# HIVE_SIGHT_MISC.net
KiCad netlist of a schematic drawn in Altium Designer
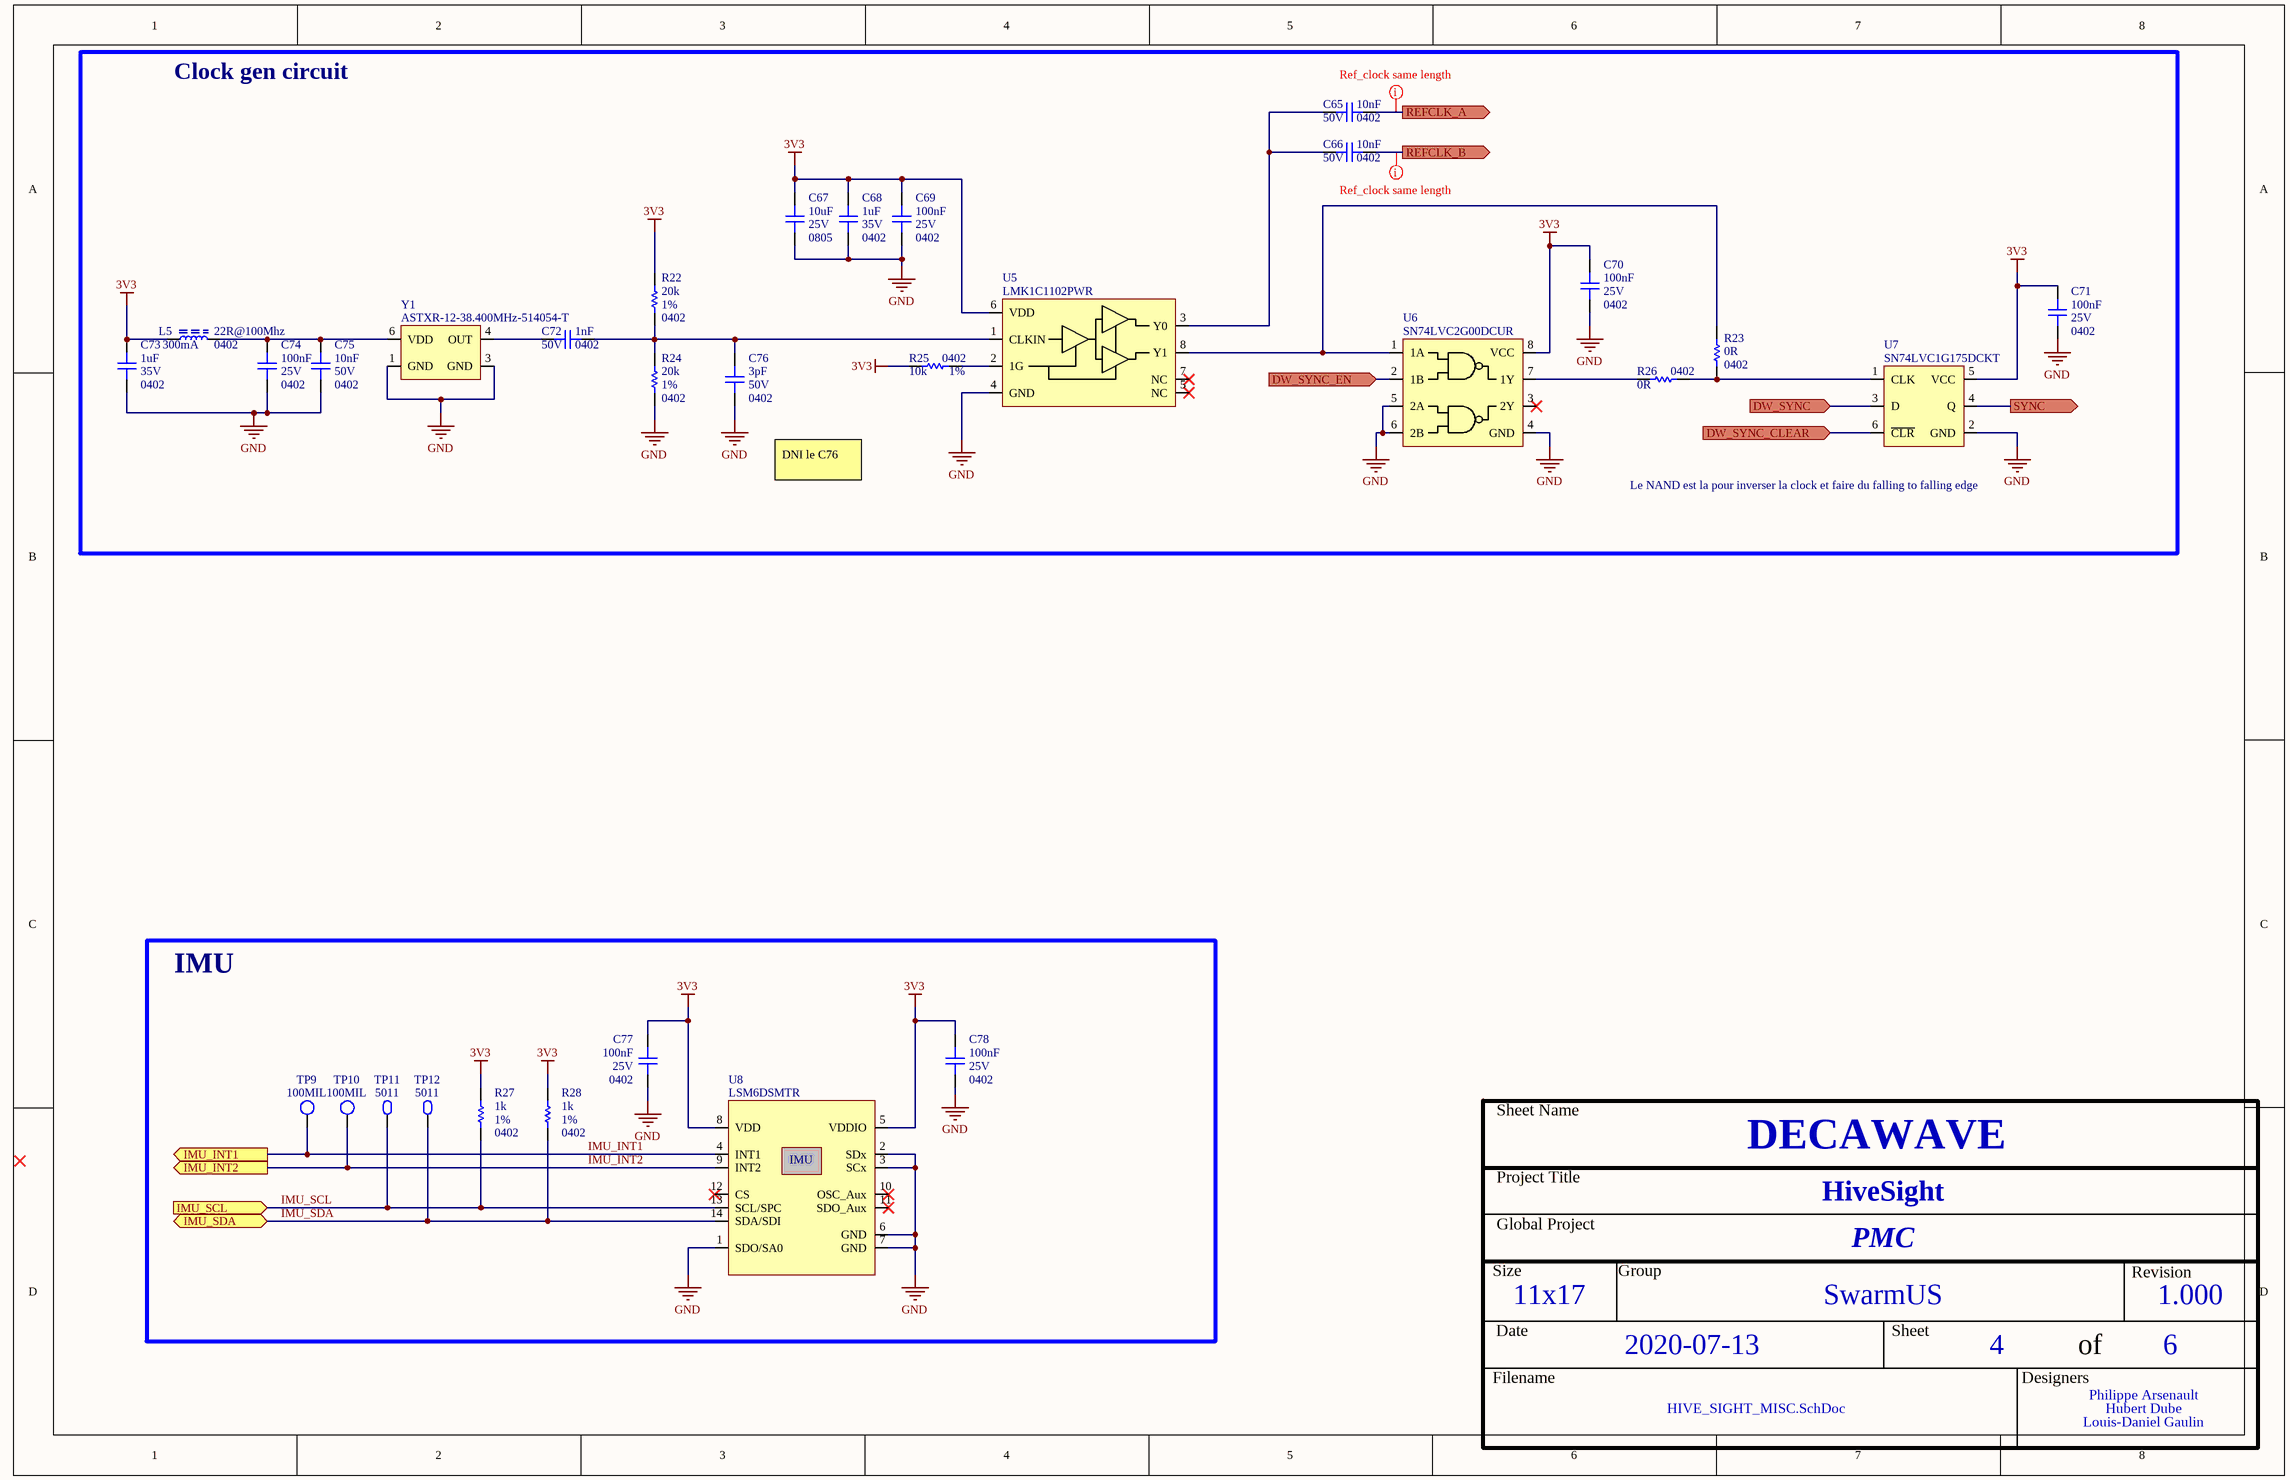
[diagram p0: HIVE_SIGHT_MISC.SchDoc]

(export (version "E")
  (design (tool "Eeschema 10.0.6"))
  (components
    (comp (ref "C65")
      (value "10nF")
      (footprint "GRAMS_MASTER_LIB_PCB:CAP_CER_0402")
      (description "CAP - CER 10nF 50V X7R 20% - 0402")
      (fields
        (field (name "TOLERANCE") "20%")
        (field (name "PACKAGE") "0402")
        (field (name "VOLTAGE RATING") "50V")
        (field (name "Comment") "C0402C103M5RACTU")
        (field (name "CREATEDBY/DATE") "Keven Deslandes - 2018/11/09")
        (field (name "VERIFIEDBY") "Nicolas Roy - 2018/12/11")
      )
      (libsource (lib "GRAMS_MASTER_LIB_SCH") (part "CAP_CER_C0402C103M5RACTU"))
    )
    (comp (ref "C66")
      (value "10nF")
      (footprint "GRAMS_MASTER_LIB_PCB:CAP_CER_0402")
      (description "CAP - CER 10nF 50V X7R 20% - 0402")
      (fields
        (field (name "TOLERANCE") "20%")
        (field (name "PACKAGE") "0402")
        (field (name "VOLTAGE RATING") "50V")
        (field (name "Comment") "C0402C103M5RACTU")
        (field (name "CREATEDBY/DATE") "Keven Deslandes - 2018/11/09")
        (field (name "VERIFIEDBY") "Nicolas Roy - 2018/12/11")
      )
      (libsource (lib "GRAMS_MASTER_LIB_SCH") (part "CAP_CER_C0402C103M5RACTU"))
    )
    (comp (ref "C67")
      (value "10uF")
      (footprint "GRAMS_MASTER_LIB_PCB:CAP_CER_0805")
      (description "CAP - CER 10UF 10% 25V X7S - 0805")
      (fields
        (field (name "TOLERANCE") "10%")
        (field (name "PACKAGE") "0805")
        (field (name "VOLTAGE RATING") "25V")
        (field (name "Comment") "GRM21BC71E106KE11L")
        (field (name "CREATEDBY/DATE") "Caroline Paulin / 8 août 2018")
        (field (name "VERIFIEDBY") "Nicolas V. (2019-01-22)")
      )
      (libsource (lib "GRAMS_MASTER_LIB_SCH") (part "CAP_CER_GRM21BC71E106KE11L"))
    )
    (comp (ref "C68")
      (value "1uF")
      (footprint "GRAMS_MASTER_LIB_PCB:CAP_CER_0402")
      (description "CAP - CER 1uF 10% 35V X5R - 0402")
      (fields
        (field (name "TOLERANCE") "10%")
        (field (name "PACKAGE") "0402")
        (field (name "VOLTAGE RATING") "35V")
        (field (name "Comment") "CL05A105KL5NRNC")
        (field (name "CREATEDBY/DATE") "Nicolas Roy 2018-10-03")
        (field (name "VERIFIEDBY") "Caroline Paulin - 18 janv 2019")
      )
      (libsource (lib "GRAMS_MASTER_LIB_SCH") (part "CAP_CER_CL05A105KL5NRNC"))
    )
    (comp (ref "C69")
      (value "100nF")
      (footprint "GRAMS_MASTER_LIB_PCB:CAP_CER_0402")
      (description "CAP - CER 0.1uF 10% 25V X5R - 0402")
      (fields
        (field (name "TOLERANCE") "10%")
        (field (name "PACKAGE") "0402")
        (field (name "VOLTAGE RATING") "25V")
        (field (name "Comment") "CL05A104KA5NNNC")
        (field (name "CREATEDBY/DATE") "Keven Deslandes - 2018/09/26")
        (field (name "VERIFIEDBY") "Nicolas Roy - 2018/12/11")
      )
      (libsource (lib "GRAMS_MASTER_LIB_SCH") (part "CAP_CER_CL05A104KA5NNNC"))
    )
    (comp (ref "C70")
      (value "100nF")
      (footprint "GRAMS_MASTER_LIB_PCB:CAP_CER_0402")
      (description "CAP - CER 0.1uF 10% 25V X5R - 0402")
      (fields
        (field (name "TOLERANCE") "10%")
        (field (name "PACKAGE") "0402")
        (field (name "VOLTAGE RATING") "25V")
        (field (name "Comment") "CL05A104KA5NNNC")
        (field (name "CREATEDBY/DATE") "Keven Deslandes - 2018/09/26")
        (field (name "VERIFIEDBY") "Nicolas Roy - 2018/12/11")
      )
      (libsource (lib "GRAMS_MASTER_LIB_SCH") (part "CAP_CER_CL05A104KA5NNNC"))
    )
    (comp (ref "C71")
      (value "100nF")
      (footprint "GRAMS_MASTER_LIB_PCB:CAP_CER_0402")
      (description "CAP - CER 0.1uF 10% 25V X5R - 0402")
      (fields
        (field (name "TOLERANCE") "10%")
        (field (name "PACKAGE") "0402")
        (field (name "VOLTAGE RATING") "25V")
        (field (name "Comment") "CL05A104KA5NNNC")
        (field (name "CREATEDBY/DATE") "Keven Deslandes - 2018/09/26")
        (field (name "VERIFIEDBY") "Nicolas Roy - 2018/12/11")
      )
      (libsource (lib "GRAMS_MASTER_LIB_SCH") (part "CAP_CER_CL05A104KA5NNNC"))
    )
    (comp (ref "C72")
      (value "1nF")
      (footprint "CAP_CER_0402")
      (description "CAP - CER 1nF 10% 50V X7R - 0402")
      (fields
        (field (name "TOLERANCE") "10%")
        (field (name "PACKAGE") "0402")
        (field (name "VOLTAGE RATING") "50V")
        (field (name "Comment") "CC0402KRX7R9BB102")
        (field (name "CREATEDBY/DATE") "Jonathan Bouchard 2019-04-06")
        (field (name "VERIFIEDBY") "Nicolas V. (2019-04-30)")
      )
      (libsource (lib "GRAMS_MASTER_LIB_SCH") (part "CAP_CER_CC0402KRX7R9BB102"))
    )
    (comp (ref "C73")
      (value "1uF")
      (footprint "GRAMS_MASTER_LIB_PCB:CAP_CER_0402")
      (description "CAP - CER 1uF 10% 35V X5R - 0402")
      (fields
        (field (name "TOLERANCE") "10%")
        (field (name "PACKAGE") "0402")
        (field (name "VOLTAGE RATING") "35V")
        (field (name "Comment") "CL05A105KL5NRNC")
        (field (name "CREATEDBY/DATE") "Nicolas Roy 2018-10-03")
        (field (name "VERIFIEDBY") "Caroline Paulin - 18 janv 2019")
      )
      (libsource (lib "GRAMS_MASTER_LIB_SCH") (part "CAP_CER_CL05A105KL5NRNC"))
    )
    (comp (ref "C74")
      (value "100nF")
      (footprint "GRAMS_MASTER_LIB_PCB:CAP_CER_0402")
      (description "CAP - CER 0.1uF 10% 25V X5R - 0402")
      (fields
        (field (name "TOLERANCE") "10%")
        (field (name "PACKAGE") "0402")
        (field (name "VOLTAGE RATING") "25V")
        (field (name "Comment") "CL05A104KA5NNNC")
        (field (name "CREATEDBY/DATE") "Keven Deslandes - 2018/09/26")
        (field (name "VERIFIEDBY") "Nicolas Roy - 2018/12/11")
      )
      (libsource (lib "GRAMS_MASTER_LIB_SCH") (part "CAP_CER_CL05A104KA5NNNC"))
    )
    (comp (ref "C75")
      (value "10nF")
      (footprint "GRAMS_MASTER_LIB_PCB:CAP_CER_0402")
      (description "CAP - CER 10nF 50V X7R 20% - 0402")
      (fields
        (field (name "TOLERANCE") "20%")
        (field (name "PACKAGE") "0402")
        (field (name "VOLTAGE RATING") "50V")
        (field (name "Comment") "C0402C103M5RACTU")
        (field (name "CREATEDBY/DATE") "Keven Deslandes - 2018/11/09")
        (field (name "VERIFIEDBY") "Nicolas Roy - 2018/12/11")
      )
      (libsource (lib "GRAMS_MASTER_LIB_SCH") (part "CAP_CER_C0402C103M5RACTU"))
    )
    (comp (ref "C76")
      (value "3pF")
      (footprint "CAP_CER_0402")
      (description "CAP - CER 3pF 50V ±0.25pF C0G, NP0 - 0402")
      (fields
        (field (name "TOLERANCE") "±0.25pF")
        (field (name "PACKAGE") "0402")
        (field (name "VOLTAGE RATING") "50V")
        (field (name "Comment") "CC0402CRNPO9BN3R0")
        (field (name "CREATEDBY/DATE") "Philippe Arsenault/ 2020-07-24")
        (field (name "VERIFIEDBY") "Louis-Daniel Gaulin / 2020-07-29")
      )
      (libsource (lib "SWARMUS_LIB") (part "CAP_CER_CC0402CRNPO9BN3R0"))
    )
    (comp (ref "C77")
      (value "100nF")
      (footprint "GRAMS_MASTER_LIB_PCB:CAP_CER_0402")
      (description "CAP - CER 0.1µF 10% 25V X7R - 0402")
      (fields
        (field (name "TOLERANCE") "10%")
        (field (name "PACKAGE") "0402")
        (field (name "VOLTAGE RATING") "25V")
        (field (name "Comment") "CGA2B3X7R1E104K050BB")
        (field (name "CREATEDBY/DATE") "Nicolas Roy 2018-11-07")
        (field (name "VERIFIEDBY") "Nicolas V. (2019-01-22)")
      )
      (libsource (lib "GRAMS_MASTER_LIB_SCH") (part "CAP_CER_CGA2B3X7R1E104K050BB"))
    )
    (comp (ref "C78")
      (value "100nF")
      (footprint "GRAMS_MASTER_LIB_PCB:CAP_CER_0402")
      (description "CAP - CER 0.1µF 10% 25V X7R - 0402")
      (fields
        (field (name "TOLERANCE") "10%")
        (field (name "PACKAGE") "0402")
        (field (name "VOLTAGE RATING") "25V")
        (field (name "Comment") "CGA2B3X7R1E104K050BB")
        (field (name "CREATEDBY/DATE") "Nicolas Roy 2018-11-07")
        (field (name "VERIFIEDBY") "Nicolas V. (2019-01-22)")
      )
      (libsource (lib "GRAMS_MASTER_LIB_SCH") (part "CAP_CER_CGA2B3X7R1E104K050BB"))
    )
    (comp (ref "L5")
      (value "22R@100Mhz")
      (footprint "FER_0402")
      (description "FER - FERRITE BEAD 22 OHM - 0402")
      (fields
        (field (name "CURRENT RATING") "300mA")
        (field (name "PACKAGE") "0402")
        (field (name "Comment") "BLM15BB220SN1D")
        (field (name "CREATEDBY/DATE") "Philippe Arsenault/2020-11-03")
      )
      (libsource (lib "a_Valider_PA") (part "FER_BLM15BB220SN1D"))
    )
    (comp (ref "R22")
      (value "20k")
      (footprint "GRAMS_MASTER_LIB_PCB:RES_0402")
      (description "RES - 20K 1% 1/16W  - 0402")
      (fields
        (field (name "TOLERANCE") "1%")
        (field (name "PACKAGE") "0402")
        (field (name "Comment") "RC0402FR-0720KL")
        (field (name "CREATEDBY/DATE") "Keven Deslandes 2018-10-18")
        (field (name "VERIFIEDBY") "Caroline Paulin - 7 janv 2019")
      )
      (libsource (lib "GRAMS_MASTER_LIB_SCH") (part "RES_RC0402FR-0720KL"))
    )
    (comp (ref "R23")
      (value "0R")
      (footprint "GRAMS_MASTER_LIB_PCB:RES_0402")
      (description "RES - 0R 1/16W 1A  - 0402")
      (fields
        (field (name "PACKAGE") "0402")
        (field (name "Comment") "RC0402FR-070RL")
        (field (name "CREATEDBY/DATE") "Keven Deslandes 2018-09-12")
        (field (name "VERIFIEDBY") "Caroline Paulin - 27 fév 2019")
      )
      (libsource (lib "GRAMS_MASTER_LIB_SCH") (part "RES_RC0402FR-070RL"))
    )
    (comp (ref "R24")
      (value "20k")
      (footprint "GRAMS_MASTER_LIB_PCB:RES_0402")
      (description "RES - 20K 1% 1/16W  - 0402")
      (fields
        (field (name "TOLERANCE") "1%")
        (field (name "PACKAGE") "0402")
        (field (name "Comment") "RC0402FR-0720KL")
        (field (name "CREATEDBY/DATE") "Keven Deslandes 2018-10-18")
        (field (name "VERIFIEDBY") "Caroline Paulin - 7 janv 2019")
      )
      (libsource (lib "GRAMS_MASTER_LIB_SCH") (part "RES_RC0402FR-0720KL"))
    )
    (comp (ref "R25")
      (value "10k")
      (footprint "GRAMS_MASTER_LIB_PCB:RES_0402")
      (description "RES - 10K OHMS 1% 1/16W - 0402")
      (fields
        (field (name "TOLERANCE") "1%")
        (field (name "PACKAGE") "0402")
        (field (name "Comment") "RC0402FR-0710KL")
        (field (name "CREATEDBY/DATE") "Nicolas V. (2018-11-20)")
        (field (name "VERIFIEDBY") "Nicolas V. (2018-11-20)")
      )
      (libsource (lib "GRAMS_MASTER_LIB_SCH") (part "RES_RC0402FR-0710KL"))
    )
    (comp (ref "R26")
      (value "0R")
      (footprint "GRAMS_MASTER_LIB_PCB:RES_0402")
      (description "RES - 0R 1/16W 1A  - 0402")
      (fields
        (field (name "PACKAGE") "0402")
        (field (name "Comment") "RC0402FR-070RL")
        (field (name "CREATEDBY/DATE") "Keven Deslandes 2018-09-12")
        (field (name "VERIFIEDBY") "Caroline Paulin - 27 fév 2019")
      )
      (libsource (lib "GRAMS_MASTER_LIB_SCH") (part "RES_RC0402FR-070RL"))
    )
    (comp (ref "R27")
      (value "1k")
      (footprint "GRAMS_MASTER_LIB_PCB:RES_0402")
      (description "RES - 1K OHM 1% 1/16W - 0402")
      (fields
        (field (name "TOLERANCE") "1%")
        (field (name "PACKAGE") "0402")
        (field (name "Comment") "RC0402FR-071KL")
        (field (name "CREATEDBY/DATE") "Jonathan Bouchard 2018-07-05")
        (field (name "VERIFIEDBY") "Arnaud Samson 16-07-18")
      )
      (libsource (lib "GRAMS_MASTER_LIB_SCH") (part "RES_RC0402FR-071KL"))
    )
    (comp (ref "R28")
      (value "1k")
      (footprint "GRAMS_MASTER_LIB_PCB:RES_0402")
      (description "RES - 1K OHM 1% 1/16W - 0402")
      (fields
        (field (name "TOLERANCE") "1%")
        (field (name "PACKAGE") "0402")
        (field (name "Comment") "RC0402FR-071KL")
        (field (name "CREATEDBY/DATE") "Jonathan Bouchard 2018-07-05")
        (field (name "VERIFIEDBY") "Arnaud Samson 16-07-18")
      )
      (libsource (lib "GRAMS_MASTER_LIB_SCH") (part "RES_RC0402FR-071KL"))
    )
    (comp (ref "TP9")
      (value "100MIL")
      (footprint "grams_master_lib_pcb:TPO_TH_ROUND_100MIL")
      (description "TPO - TEST POINT ROUND TH  - 100MIL")
      (fields
        (field (name "CREATEDBY/DATE") "Louis-Daniel Gaulin/ 14/01/2020")
        (field (name "VERIFIEDBY") "C.Paulin - 21/01/2020")
      )
      (libsource (lib "GRAMS_MASTER_LIB_SCH") (part "TPO_TH_ROUND_100MIL"))
    )
    (comp (ref "TP10")
      (value "100MIL")
      (footprint "grams_master_lib_pcb:TPO_TH_ROUND_100MIL")
      (description "TPO - TEST POINT ROUND TH  - 100MIL")
      (fields
        (field (name "CREATEDBY/DATE") "Louis-Daniel Gaulin/ 14/01/2020")
        (field (name "VERIFIEDBY") "C.Paulin - 21/01/2020")
      )
      (libsource (lib "GRAMS_MASTER_LIB_SCH") (part "TPO_TH_ROUND_100MIL"))
    )
    (comp (ref "TP11")
      (value "5011")
      (footprint "TPO_5011")
      (description "TPO - TEST POINT - TH")
      (fields
        (field (name "CREATEDBY/DATE") "Louis-Daniel Gauli / 02-11-2020")
        (field (name "VERIFIEDBY") "Philippe Arsenault/2020-11-06")
      )
      (libsource (lib "SWARMUS_LIB") (part "TPO_5011"))
    )
    (comp (ref "TP12")
      (value "5011")
      (footprint "TPO_5011")
      (description "TPO - TEST POINT - TH")
      (fields
        (field (name "CREATEDBY/DATE") "Louis-Daniel Gauli / 02-11-2020")
        (field (name "VERIFIEDBY") "Philippe Arsenault/2020-11-06")
      )
      (libsource (lib "SWARMUS_LIB") (part "TPO_5011"))
    )
    (comp (ref "U5")
      (value "LMK1C1102PWR")
      (footprint "COM_BUF_LMK1C1102PWR")
      (description "COM - BUF - Clock buffer 3V3, 2V5, 1V8 2 Channel - TSSOP 8")
      (fields
        (field (name "CREATEDBY/DATE") "Philippe Arsenault/20-07-2020")
        (field (name "VERIFIEDBY") "Louis-Daniel Gaulin / 23-07-2020")
      )
      (libsource (lib "SWARMUS_LIB") (part "COM_BUF_LMK1C1102PWR"))
    )
    (comp (ref "U6")
      (value "SN74LVC2G00DCUR")
      (footprint "LOG_NAND_SN74LVC2G00DCUR")
      (description "LOG_NAND - GATE NAND 2CH 2-INP - 8-VSSOP")
      (fields
        (field (name "CREATEDBY/DATE") "Philippe Arsenault/21-07-2020")
        (field (name "VERIFIEDBY") "Louis-Daniel Gaulin / 23-07-2020")
      )
      (libsource (lib "SWARMUS_LIB") (part "LOG_NAND_SN74LVC2G00DCUR"))
    )
    (comp (ref "U7")
      (value "SN74LVC1G175DCKT")
      (footprint "LOG_FLIPFLOP_SN74LVC1G175DCKT")
      (description "LOG_FLIPFLOP - Single D flip-flop with Asynchronous clear - SOT-363")
      (fields
        (field (name "CREATEDBY/DATE") "Philippe Arsenault/21-07-2020")
        (field (name "VERIFIEDBY") "Louis-Daniel Gaulin / 03-10-2020")
      )
      (libsource (lib "SWARMUS_LIB") (part "LOG_FLIPFLOP_SN74LVC1G175DCKT"))
    )
    (comp (ref "U8")
      (value "LSM6DSMTR")
      (footprint "SEN_IMU_LSM6DSMTR")
      (description "SEN_IMU -  ACCEL/GYRO 6 Axis I2C/SPI - 14-VFLGA")
      (fields
        (field (name "CREATEDBY/DATE") "Louis-Daniel Gaulin / 06-10-2020")
        (field (name "VERIFIEDBY") "Philippe Arsenault/2020-11-06")
      )
      (libsource (lib "SWARMUS_LIB") (part "SEN_IMU_LSM6DSMTR"))
    )
    (comp (ref "Y1")
      (value "ASTXR-12-38.400MHz-514054-T")
      (footprint "OSC_ASTXR-12-38.400MHZ-514054-T")
      (fields
        (field (name "CREATEDBY/DATE") "Philippe Arsenault/18-07-2020")
        (field (name "VERIFIEDBY") "Louis-Daniel Gaulin / 03-10-2020")
      )
      (libsource (lib "SWARMUS_LIB") (part "OSC_ASTXR-12-38.400MHz-514054-T"))
    )
  )
  (nets
    (net (code "1") (name "/DW_SYNC") (class "Default")
      (node (ref "U7") (pin "3") (pinfunction "D_3") (pintype "passive"))
    )
    (net (code "2") (name "/DW_SYNC_CLEAR") (class "Default")
      (node (ref "U7") (pin "6") (pinfunction "CLR_6") (pintype "passive"))
    )
    (net (code "3") (name "/DW_SYNC_EN") (class "Default")
      (node (ref "U6") (pin "2") (pinfunction "1B_2") (pintype "passive"))
    )
    (net (code "4") (name "/IMU_INT1") (class "Default")
      (node (ref "TP9") (pin "1") (pinfunction "1_1") (pintype "passive"))
      (node (ref "U8") (pin "4") (pinfunction "INT1_4") (pintype "passive"))
    )
    (net (code "5") (name "/IMU_INT2") (class "Default")
      (node (ref "TP10") (pin "1") (pinfunction "1_1") (pintype "passive"))
      (node (ref "U8") (pin "9") (pinfunction "INT2_9") (pintype "passive"))
    )
    (net (code "6") (name "/IMU_SCL") (class "Default")
      (node (ref "R27") (pin "2") (pinfunction "2_2") (pintype "passive"))
      (node (ref "TP11") (pin "1") (pinfunction "1_1") (pintype "passive"))
      (node (ref "U8") (pin "13") (pinfunction "SCL/SPC_13") (pintype "passive"))
    )
    (net (code "7") (name "/IMU_SDA") (class "Default")
      (node (ref "R28") (pin "2") (pinfunction "2_2") (pintype "passive"))
      (node (ref "TP12") (pin "1") (pinfunction "1_1") (pintype "passive"))
      (node (ref "U8") (pin "14") (pinfunction "SDA/SDI_14") (pintype "passive"))
    )
    (net (code "8") (name "/REFCLK_A") (class "Default")
      (node (ref "C65") (pin "1") (pinfunction "1_1") (pintype "passive"))
    )
    (net (code "9") (name "/REFCLK_B") (class "Default")
      (node (ref "C66") (pin "1") (pinfunction "1_1") (pintype "passive"))
    )
    (net (code "10") (name "/SYNC") (class "Default")
      (node (ref "U7") (pin "4") (pinfunction "Q_4") (pintype "passive"))
    )
    (net (code "11") (name "3V3") (class "Default")
      (node (ref "C67") (pin "2") (pinfunction "2_2") (pintype "passive"))
      (node (ref "C68") (pin "2") (pinfunction "2_2") (pintype "passive"))
      (node (ref "C69") (pin "2") (pinfunction "2_2") (pintype "passive"))
      (node (ref "C70") (pin "2") (pinfunction "2_2") (pintype "passive"))
      (node (ref "C71") (pin "1") (pinfunction "1_1") (pintype "passive"))
      (node (ref "C73") (pin "2") (pinfunction "2_2") (pintype "passive"))
      (node (ref "C77") (pin "1") (pinfunction "1_1") (pintype "passive"))
      (node (ref "C78") (pin "1") (pinfunction "1_1") (pintype "passive"))
      (node (ref "L5") (pin "1") (pinfunction "1_1") (pintype "passive"))
      (node (ref "R22") (pin "2") (pinfunction "2_2") (pintype "passive"))
      (node (ref "R25") (pin "2") (pinfunction "2_2") (pintype "passive"))
      (node (ref "R27") (pin "1") (pinfunction "1_1") (pintype "passive"))
      (node (ref "R28") (pin "1") (pinfunction "1_1") (pintype "passive"))
      (node (ref "U5") (pin "6") (pinfunction "VDD_6") (pintype "passive"))
      (node (ref "U6") (pin "8") (pinfunction "VCC_8") (pintype "passive"))
      (node (ref "U7") (pin "5") (pinfunction "VCC_5") (pintype "passive"))
      (node (ref "U8") (pin "5") (pinfunction "VDDIO_5") (pintype "passive"))
      (node (ref "U8") (pin "8") (pinfunction "VDD_8") (pintype "passive"))
    )
    (net (code "12") (name "GND") (class "Default")
      (node (ref "C67") (pin "1") (pinfunction "1_1") (pintype "passive"))
      (node (ref "C68") (pin "1") (pinfunction "1_1") (pintype "passive"))
      (node (ref "C69") (pin "1") (pinfunction "1_1") (pintype "passive"))
      (node (ref "C70") (pin "1") (pinfunction "1_1") (pintype "passive"))
      (node (ref "C71") (pin "2") (pinfunction "2_2") (pintype "passive"))
      (node (ref "C73") (pin "1") (pinfunction "1_1") (pintype "passive"))
      (node (ref "C74") (pin "1") (pinfunction "1_1") (pintype "passive"))
      (node (ref "C75") (pin "1") (pinfunction "1_1") (pintype "passive"))
      (node (ref "C76") (pin "1") (pinfunction "1_1") (pintype "passive"))
      (node (ref "C77") (pin "2") (pinfunction "2_2") (pintype "passive"))
      (node (ref "C78") (pin "2") (pinfunction "2_2") (pintype "passive"))
      (node (ref "R24") (pin "1") (pinfunction "1_1") (pintype "passive"))
      (node (ref "U5") (pin "4") (pinfunction "GND_4") (pintype "passive"))
      (node (ref "U6") (pin "4") (pinfunction "GND_4") (pintype "passive"))
      (node (ref "U6") (pin "5") (pinfunction "2A_5") (pintype "passive"))
      (node (ref "U6") (pin "6") (pinfunction "2B_6") (pintype "passive"))
      (node (ref "U7") (pin "2") (pinfunction "GND_2") (pintype "passive"))
      (node (ref "U8") (pin "1") (pinfunction "SDO/SA0_1") (pintype "passive"))
      (node (ref "U8") (pin "2") (pinfunction "SDx_2") (pintype "passive"))
      (node (ref "U8") (pin "3") (pinfunction "SCx_3") (pintype "passive"))
      (node (ref "U8") (pin "6") (pinfunction "GND_6") (pintype "passive"))
      (node (ref "U8") (pin "7") (pinfunction "GND_7") (pintype "passive"))
      (node (ref "Y1") (pin "1") (pinfunction "GND_1") (pintype "passive"))
      (node (ref "Y1") (pin "3") (pinfunction "GND_3") (pintype "passive"))
    )
    (net (code "13") (name "Net-(U5-1G)") (class "Default")
      (node (ref "R25") (pin "1") (pinfunction "1_1") (pintype "passive"))
      (node (ref "U5") (pin "2") (pinfunction "1G_2") (pintype "passive"))
    )
    (net (code "14") (name "Net-(U5-CLKIN)") (class "Default")
      (node (ref "C72") (pin "1") (pinfunction "1_1") (pintype "passive"))
      (node (ref "C76") (pin "2") (pinfunction "2_2") (pintype "passive"))
      (node (ref "R22") (pin "1") (pinfunction "1_1") (pintype "passive"))
      (node (ref "R24") (pin "2") (pinfunction "2_2") (pintype "passive"))
      (node (ref "U5") (pin "1") (pinfunction "CLKIN_1") (pintype "passive"))
    )
    (net (code "15") (name "Net-(U5-Y0)") (class "Default")
      (node (ref "C65") (pin "2") (pinfunction "2_2") (pintype "passive"))
      (node (ref "C66") (pin "2") (pinfunction "2_2") (pintype "passive"))
      (node (ref "U5") (pin "3") (pinfunction "Y0_3") (pintype "passive"))
    )
    (net (code "16") (name "Net-(U5-Y1)") (class "Default")
      (node (ref "R23") (pin "2") (pinfunction "2_2") (pintype "passive"))
      (node (ref "U5") (pin "8") (pinfunction "Y1_8") (pintype "passive"))
      (node (ref "U6") (pin "1") (pinfunction "1A_1") (pintype "passive"))
    )
    (net (code "17") (name "Net-(U6-1Y)") (class "Default")
      (node (ref "R26") (pin "2") (pinfunction "2_2") (pintype "passive"))
      (node (ref "U6") (pin "7") (pinfunction "1Y_7") (pintype "passive"))
    )
    (net (code "18") (name "Net-(U7-CLK)") (class "Default")
      (node (ref "R23") (pin "1") (pinfunction "1_1") (pintype "passive"))
      (node (ref "R26") (pin "1") (pinfunction "1_1") (pintype "passive"))
      (node (ref "U7") (pin "1") (pinfunction "CLK_1") (pintype "passive"))
    )
    (net (code "19") (name "Net-(Y1-OUT)") (class "Default")
      (node (ref "C72") (pin "2") (pinfunction "2_2") (pintype "passive"))
      (node (ref "Y1") (pin "4") (pinfunction "OUT_4") (pintype "passive"))
    )
    (net (code "20") (name "Net-(Y1-VDD)") (class "Default")
      (node (ref "C74") (pin "2") (pinfunction "2_2") (pintype "passive"))
      (node (ref "C75") (pin "2") (pinfunction "2_2") (pintype "passive"))
      (node (ref "L5") (pin "2") (pinfunction "2_2") (pintype "passive"))
      (node (ref "Y1") (pin "6") (pinfunction "VDD_6") (pintype "passive"))
    )
    (net (code "21") (name "unconnected-(U5-NC-Pad5)") (class "Default")
      (node (ref "U5") (pin "5") (pinfunction "NC_5") (pintype "passive+no_connect"))
    )
    (net (code "22") (name "unconnected-(U5-NC-Pad7)") (class "Default")
      (node (ref "U5") (pin "7") (pinfunction "NC_7") (pintype "passive+no_connect"))
    )
    (net (code "23") (name "unconnected-(U6-2Y-Pad3)") (class "Default")
      (node (ref "U6") (pin "3") (pinfunction "2Y_3") (pintype "passive+no_connect"))
    )
    (net (code "24") (name "unconnected-(U8-CS-Pad12)") (class "Default")
      (node (ref "U8") (pin "12") (pinfunction "CS_12") (pintype "passive+no_connect"))
    )
    (net (code "25") (name "unconnected-(U8-OSC_Aux-Pad10)") (class "Default")
      (node (ref "U8") (pin "10") (pinfunction "OSC_Aux_10") (pintype "passive+no_connect"))
    )
    (net (code "26") (name "unconnected-(U8-SDO_Aux-Pad11)") (class "Default")
      (node (ref "U8") (pin "11") (pinfunction "SDO_Aux_11") (pintype "passive+no_connect"))
    )
  )
)
